# R220L.net
KiCad netlist of a schematic drawn in EAGLE
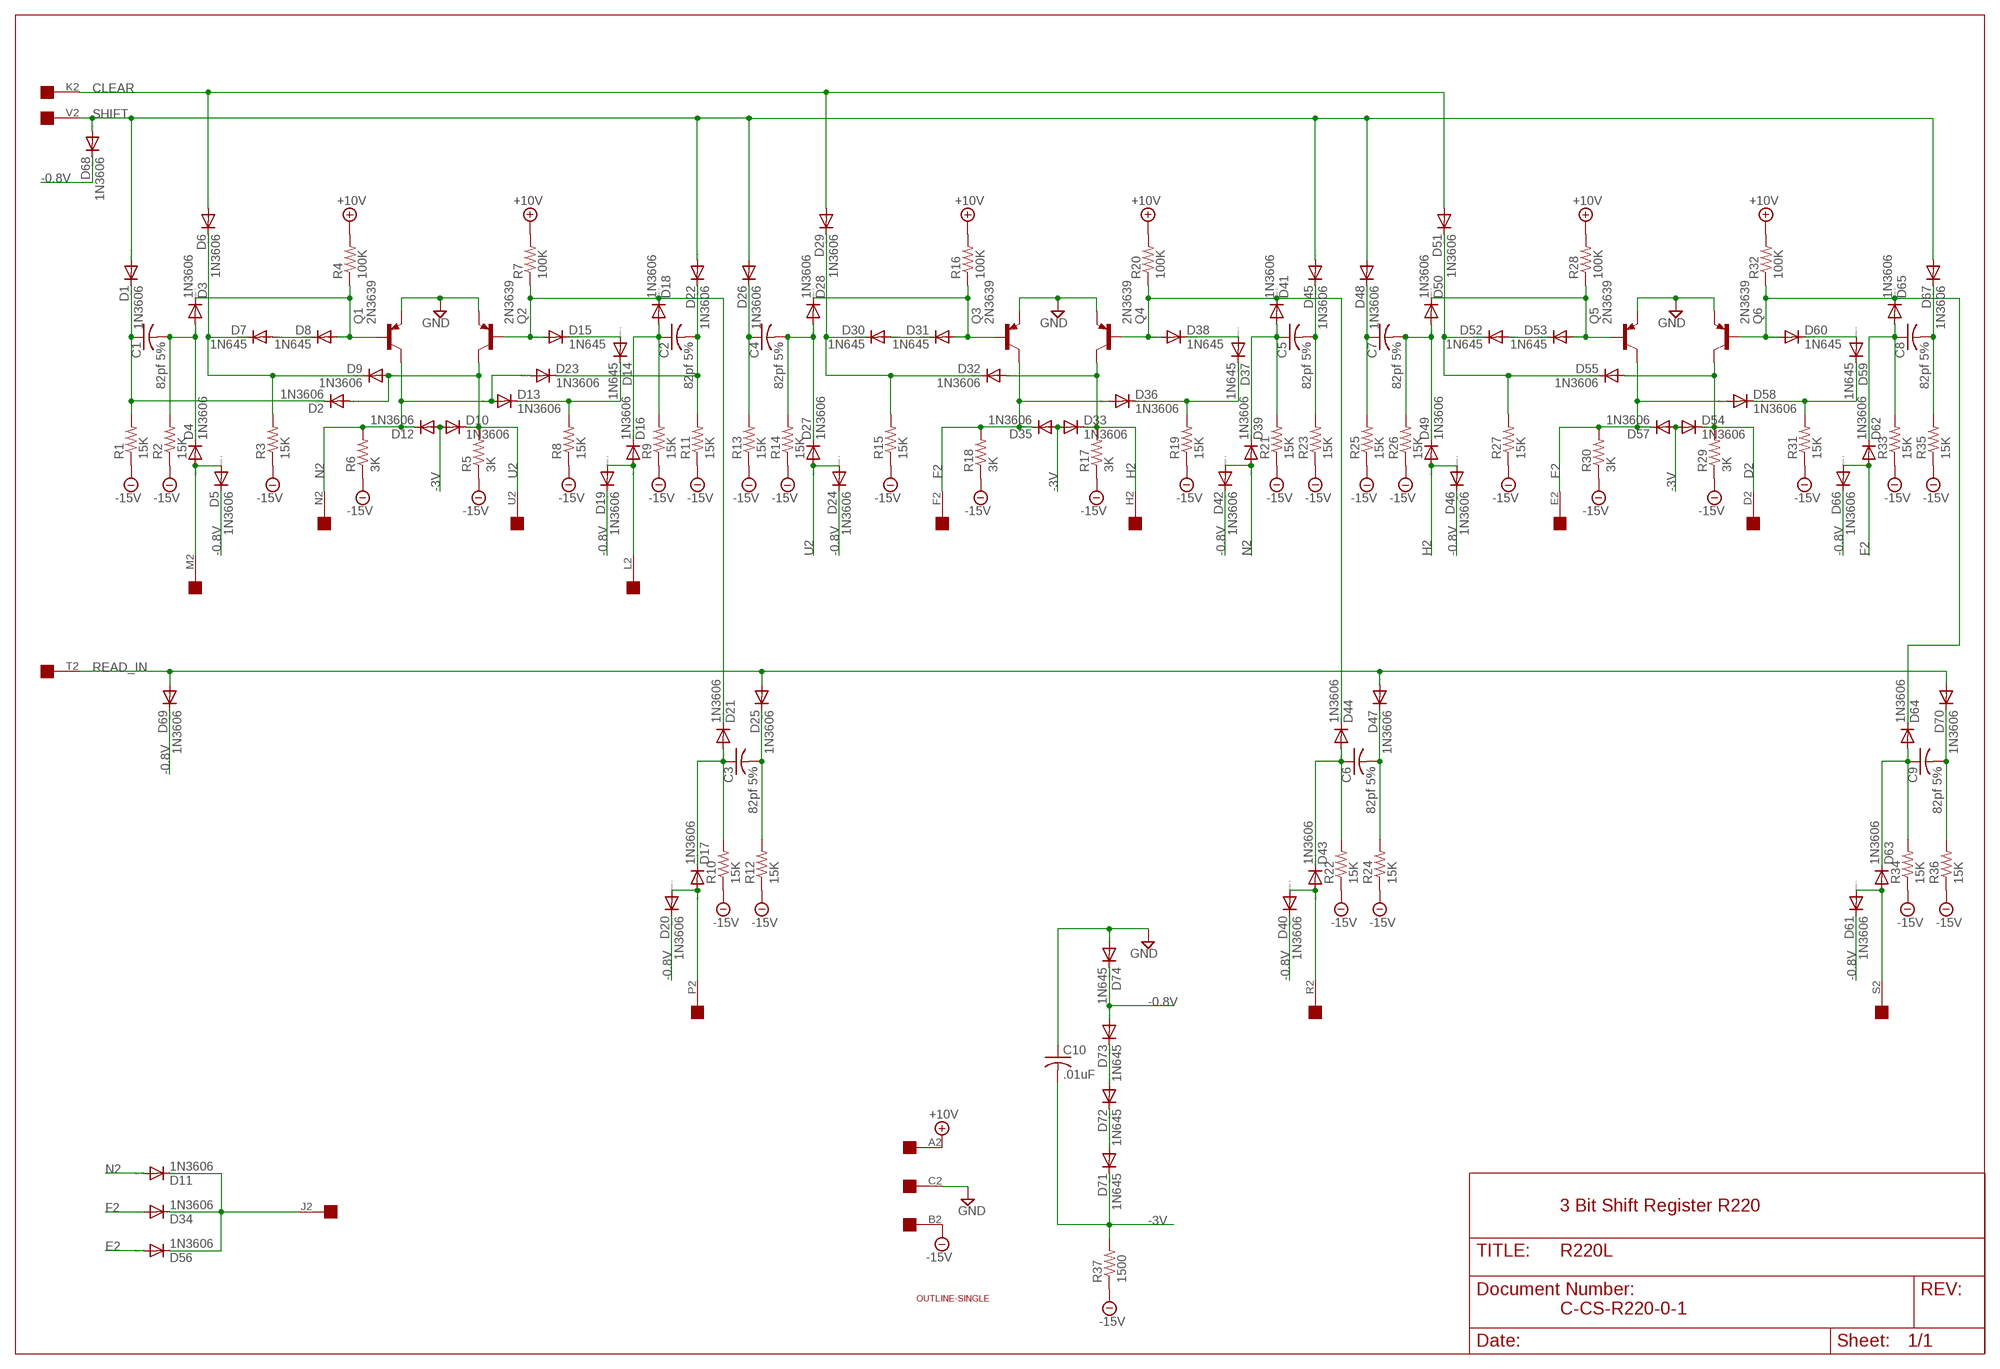
[diagram p0: schematic, sheet 1]

(export (version "E")
  (design (tool "Eeschema 10.0.6"))
  (components
    (comp (ref "C1")
      (value "82pf 5%")
      (footprint "eagle-import:C063-025X075")
      (libsource (lib "eagle-import") (part "C-US"))
    )
    (comp (ref "C2")
      (value "82pf 5%")
      (footprint "eagle-import:C063-025X075")
      (libsource (lib "eagle-import") (part "C-US"))
    )
    (comp (ref "C3")
      (value "82pf 5%")
      (footprint "eagle-import:C063-025X075")
      (libsource (lib "eagle-import") (part "C-US"))
    )
    (comp (ref "C4")
      (value "82pf 5%")
      (footprint "eagle-import:C063-025X075")
      (libsource (lib "eagle-import") (part "C-US"))
    )
    (comp (ref "C5")
      (value "82pf 5%")
      (footprint "eagle-import:C063-025X075")
      (libsource (lib "eagle-import") (part "C-US"))
    )
    (comp (ref "C6")
      (value "82pf 5%")
      (footprint "eagle-import:C063-025X075")
      (libsource (lib "eagle-import") (part "C-US"))
    )
    (comp (ref "C7")
      (value "82pf 5%")
      (footprint "eagle-import:C063-025X075")
      (libsource (lib "eagle-import") (part "C-US"))
    )
    (comp (ref "C8")
      (value "82pf 5%")
      (footprint "eagle-import:C063-025X075")
      (libsource (lib "eagle-import") (part "C-US"))
    )
    (comp (ref "C9")
      (value "82pf 5%")
      (footprint "eagle-import:C063-025X075")
      (libsource (lib "eagle-import") (part "C-US"))
    )
    (comp (ref "C10")
      (value ".01uF")
      (footprint "eagle-import:C063-025X075")
      (libsource (lib "eagle-import") (part "C-US"))
    )
    (comp (ref "D1")
      (value "1N3606")
      (footprint "eagle-import:DO35-10")
      (libsource (lib "eagle-import") (part "1N4148DO35-10"))
    )
    (comp (ref "D2")
      (value "1N3606")
      (footprint "eagle-import:DO35-10")
      (libsource (lib "eagle-import") (part "1N4148DO35-10"))
    )
    (comp (ref "D3")
      (value "1N3606")
      (footprint "eagle-import:DO35-10")
      (libsource (lib "eagle-import") (part "1N4148DO35-10"))
    )
    (comp (ref "D4")
      (value "1N3606")
      (footprint "eagle-import:DO35-10")
      (libsource (lib "eagle-import") (part "1N4148DO35-10"))
    )
    (comp (ref "D5")
      (value "1N3606")
      (footprint "eagle-import:DO35-10")
      (libsource (lib "eagle-import") (part "1N4148DO35-10"))
    )
    (comp (ref "D6")
      (value "1N3606")
      (footprint "eagle-import:DO35-10")
      (libsource (lib "eagle-import") (part "1N4148DO35-10"))
    )
    (comp (ref "D7")
      (value "1N645")
      (footprint "eagle-import:DO35-10")
      (libsource (lib "eagle-import") (part "1N4148DO35-10"))
    )
    (comp (ref "D8")
      (value "1N645")
      (footprint "eagle-import:DO35-10")
      (libsource (lib "eagle-import") (part "1N4148DO35-10"))
    )
    (comp (ref "D9")
      (value "1N3606")
      (footprint "eagle-import:DO35-10")
      (libsource (lib "eagle-import") (part "1N4148DO35-10"))
    )
    (comp (ref "D10")
      (value "1N3606")
      (footprint "eagle-import:DO35-10")
      (libsource (lib "eagle-import") (part "1N4148DO35-10"))
    )
    (comp (ref "D11")
      (value "1N3606")
      (footprint "eagle-import:DO35-10")
      (libsource (lib "eagle-import") (part "1N4148DO35-10"))
    )
    (comp (ref "D12")
      (value "1N3606")
      (footprint "eagle-import:DO35-10")
      (libsource (lib "eagle-import") (part "1N4148DO35-10"))
    )
    (comp (ref "D13")
      (value "1N3606")
      (footprint "eagle-import:DO35-10")
      (libsource (lib "eagle-import") (part "1N4148DO35-10"))
    )
    (comp (ref "D14")
      (value "1N645")
      (footprint "eagle-import:DO35-10")
      (libsource (lib "eagle-import") (part "1N4148DO35-10"))
    )
    (comp (ref "D15")
      (value "1N645")
      (footprint "eagle-import:DO35-10")
      (libsource (lib "eagle-import") (part "1N4148DO35-10"))
    )
    (comp (ref "D16")
      (value "1N3606")
      (footprint "eagle-import:DO35-10")
      (libsource (lib "eagle-import") (part "1N4148DO35-10"))
    )
    (comp (ref "D17")
      (value "1N3606")
      (footprint "eagle-import:DO35-10")
      (libsource (lib "eagle-import") (part "1N4148DO35-10"))
    )
    (comp (ref "D18")
      (value "1N3606")
      (footprint "eagle-import:DO35-10")
      (libsource (lib "eagle-import") (part "1N4148DO35-10"))
    )
    (comp (ref "D19")
      (value "1N3606")
      (footprint "eagle-import:DO35-10")
      (libsource (lib "eagle-import") (part "1N4148DO35-10"))
    )
    (comp (ref "D20")
      (value "1N3606")
      (footprint "eagle-import:DO35-10")
      (libsource (lib "eagle-import") (part "1N4148DO35-10"))
    )
    (comp (ref "D21")
      (value "1N3606")
      (footprint "eagle-import:DO35-10")
      (libsource (lib "eagle-import") (part "1N4148DO35-10"))
    )
    (comp (ref "D22")
      (value "1N3606")
      (footprint "eagle-import:DO35-10")
      (libsource (lib "eagle-import") (part "1N4148DO35-10"))
    )
    (comp (ref "D23")
      (value "1N3606")
      (footprint "eagle-import:DO35-10")
      (libsource (lib "eagle-import") (part "1N4148DO35-10"))
    )
    (comp (ref "D24")
      (value "1N3606")
      (footprint "eagle-import:DO35-10")
      (libsource (lib "eagle-import") (part "1N4148DO35-10"))
    )
    (comp (ref "D25")
      (value "1N3606")
      (footprint "eagle-import:DO35-10")
      (libsource (lib "eagle-import") (part "1N4148DO35-10"))
    )
    (comp (ref "D26")
      (value "1N3606")
      (footprint "eagle-import:DO35-10")
      (libsource (lib "eagle-import") (part "1N4148DO35-10"))
    )
    (comp (ref "D27")
      (value "1N3606")
      (footprint "eagle-import:DO35-10")
      (libsource (lib "eagle-import") (part "1N4148DO35-10"))
    )
    (comp (ref "D28")
      (value "1N3606")
      (footprint "eagle-import:DO35-10")
      (libsource (lib "eagle-import") (part "1N4148DO35-10"))
    )
    (comp (ref "D29")
      (value "1N3606")
      (footprint "eagle-import:DO35-10")
      (libsource (lib "eagle-import") (part "1N4148DO35-10"))
    )
    (comp (ref "D30")
      (value "1N645")
      (footprint "eagle-import:DO35-10")
      (libsource (lib "eagle-import") (part "1N4148DO35-10"))
    )
    (comp (ref "D31")
      (value "1N645")
      (footprint "eagle-import:DO35-10")
      (libsource (lib "eagle-import") (part "1N4148DO35-10"))
    )
    (comp (ref "D32")
      (value "1N3606")
      (footprint "eagle-import:DO35-10")
      (libsource (lib "eagle-import") (part "1N4148DO35-10"))
    )
    (comp (ref "D33")
      (value "1N3606")
      (footprint "eagle-import:DO35-10")
      (libsource (lib "eagle-import") (part "1N4148DO35-10"))
    )
    (comp (ref "D34")
      (value "1N3606")
      (footprint "eagle-import:DO35-10")
      (libsource (lib "eagle-import") (part "1N4148DO35-10"))
    )
    (comp (ref "D35")
      (value "1N3606")
      (footprint "eagle-import:DO35-10")
      (libsource (lib "eagle-import") (part "1N4148DO35-10"))
    )
    (comp (ref "D36")
      (value "1N3606")
      (footprint "eagle-import:DO35-10")
      (libsource (lib "eagle-import") (part "1N4148DO35-10"))
    )
    (comp (ref "D37")
      (value "1N645")
      (footprint "eagle-import:DO35-10")
      (libsource (lib "eagle-import") (part "1N4148DO35-10"))
    )
    (comp (ref "D38")
      (value "1N645")
      (footprint "eagle-import:DO35-10")
      (libsource (lib "eagle-import") (part "1N4148DO35-10"))
    )
    (comp (ref "D39")
      (value "1N3606")
      (footprint "eagle-import:DO35-10")
      (libsource (lib "eagle-import") (part "1N4148DO35-10"))
    )
    (comp (ref "D40")
      (value "1N3606")
      (footprint "eagle-import:DO35-10")
      (libsource (lib "eagle-import") (part "1N4148DO35-10"))
    )
    (comp (ref "D41")
      (value "1N3606")
      (footprint "eagle-import:DO35-10")
      (libsource (lib "eagle-import") (part "1N4148DO35-10"))
    )
    (comp (ref "D42")
      (value "1N3606")
      (footprint "eagle-import:DO35-10")
      (libsource (lib "eagle-import") (part "1N4148DO35-10"))
    )
    (comp (ref "D43")
      (value "1N3606")
      (footprint "eagle-import:DO35-10")
      (libsource (lib "eagle-import") (part "1N4148DO35-10"))
    )
    (comp (ref "D44")
      (value "1N3606")
      (footprint "eagle-import:DO35-10")
      (libsource (lib "eagle-import") (part "1N4148DO35-10"))
    )
    (comp (ref "D45")
      (value "1N3606")
      (footprint "eagle-import:DO35-10")
      (libsource (lib "eagle-import") (part "1N4148DO35-10"))
    )
    (comp (ref "D46")
      (value "1N3606")
      (footprint "eagle-import:DO35-10")
      (libsource (lib "eagle-import") (part "1N4148DO35-10"))
    )
    (comp (ref "D47")
      (value "1N3606")
      (footprint "eagle-import:DO35-10")
      (libsource (lib "eagle-import") (part "1N4148DO35-10"))
    )
    (comp (ref "D48")
      (value "1N3606")
      (footprint "eagle-import:DO35-10")
      (libsource (lib "eagle-import") (part "1N4148DO35-10"))
    )
    (comp (ref "D49")
      (value "1N3606")
      (footprint "eagle-import:DO35-10")
      (libsource (lib "eagle-import") (part "1N4148DO35-10"))
    )
    (comp (ref "D50")
      (value "1N3606")
      (footprint "eagle-import:DO35-10")
      (libsource (lib "eagle-import") (part "1N4148DO35-10"))
    )
    (comp (ref "D51")
      (value "1N3606")
      (footprint "eagle-import:DO35-10")
      (libsource (lib "eagle-import") (part "1N4148DO35-10"))
    )
    (comp (ref "D52")
      (value "1N645")
      (footprint "eagle-import:DO35-10")
      (libsource (lib "eagle-import") (part "1N4148DO35-10"))
    )
    (comp (ref "D53")
      (value "1N645")
      (footprint "eagle-import:DO35-10")
      (libsource (lib "eagle-import") (part "1N4148DO35-10"))
    )
    (comp (ref "D54")
      (value "1N3606")
      (footprint "eagle-import:DO35-10")
      (libsource (lib "eagle-import") (part "1N4148DO35-10"))
    )
    (comp (ref "D55")
      (value "1N3606")
      (footprint "eagle-import:DO35-10")
      (libsource (lib "eagle-import") (part "1N4148DO35-10"))
    )
    (comp (ref "D56")
      (value "1N3606")
      (footprint "eagle-import:DO35-10")
      (libsource (lib "eagle-import") (part "1N4148DO35-10"))
    )
    (comp (ref "D57")
      (value "1N3606")
      (footprint "eagle-import:DO35-10")
      (libsource (lib "eagle-import") (part "1N4148DO35-10"))
    )
    (comp (ref "D58")
      (value "1N3606")
      (footprint "eagle-import:DO35-10")
      (libsource (lib "eagle-import") (part "1N4148DO35-10"))
    )
    (comp (ref "D59")
      (value "1N645")
      (footprint "eagle-import:DO35-10")
      (libsource (lib "eagle-import") (part "1N4148DO35-10"))
    )
    (comp (ref "D60")
      (value "1N645")
      (footprint "eagle-import:DO35-10")
      (libsource (lib "eagle-import") (part "1N4148DO35-10"))
    )
    (comp (ref "D61")
      (value "1N3606")
      (footprint "eagle-import:DO35-10")
      (libsource (lib "eagle-import") (part "1N4148DO35-10"))
    )
    (comp (ref "D62")
      (value "1N3606")
      (footprint "eagle-import:DO35-10")
      (libsource (lib "eagle-import") (part "1N4148DO35-10"))
    )
    (comp (ref "D63")
      (value "1N3606")
      (footprint "eagle-import:DO35-10")
      (libsource (lib "eagle-import") (part "1N4148DO35-10"))
    )
    (comp (ref "D64")
      (value "1N3606")
      (footprint "eagle-import:DO35-10")
      (libsource (lib "eagle-import") (part "1N4148DO35-10"))
    )
    (comp (ref "D65")
      (value "1N3606")
      (footprint "eagle-import:DO35-10")
      (libsource (lib "eagle-import") (part "1N4148DO35-10"))
    )
    (comp (ref "D66")
      (value "1N3606")
      (footprint "eagle-import:DO35-10")
      (libsource (lib "eagle-import") (part "1N4148DO35-10"))
    )
    (comp (ref "D67")
      (value "1N3606")
      (footprint "eagle-import:DO35-10")
      (libsource (lib "eagle-import") (part "1N4148DO35-10"))
    )
    (comp (ref "D68")
      (value "1N3606")
      (footprint "eagle-import:DO35-10")
      (libsource (lib "eagle-import") (part "1N4148DO35-10"))
    )
    (comp (ref "D69")
      (value "1N3606")
      (footprint "eagle-import:DO35-10")
      (libsource (lib "eagle-import") (part "1N4148DO35-10"))
    )
    (comp (ref "D70")
      (value "1N3606")
      (footprint "eagle-import:DO35-10")
      (libsource (lib "eagle-import") (part "1N4148DO35-10"))
    )
    (comp (ref "D71")
      (value "1N645")
      (footprint "eagle-import:DO35-10")
      (libsource (lib "eagle-import") (part "1N4148DO35-10"))
    )
    (comp (ref "D72")
      (value "1N645")
      (footprint "eagle-import:DO35-10")
      (libsource (lib "eagle-import") (part "1N4148DO35-10"))
    )
    (comp (ref "D73")
      (value "1N645")
      (footprint "eagle-import:DO35-10")
      (libsource (lib "eagle-import") (part "1N4148DO35-10"))
    )
    (comp (ref "D74")
      (value "1N645")
      (footprint "eagle-import:DO35-10")
      (libsource (lib "eagle-import") (part "1N4148DO35-10"))
    )
    (comp (ref "Q1")
      (value "2N3639")
      (footprint "eagle-import:TO39")
      (libsource (lib "eagle-import") (part "2N3637"))
    )
    (comp (ref "Q2")
      (value "2N3639")
      (footprint "eagle-import:TO39")
      (libsource (lib "eagle-import") (part "2N3637"))
    )
    (comp (ref "Q3")
      (value "2N3639")
      (footprint "eagle-import:TO39")
      (libsource (lib "eagle-import") (part "2N3637"))
    )
    (comp (ref "Q4")
      (value "2N3639")
      (footprint "eagle-import:TO39")
      (libsource (lib "eagle-import") (part "2N3637"))
    )
    (comp (ref "Q5")
      (value "2N3639")
      (footprint "eagle-import:TO39")
      (libsource (lib "eagle-import") (part "2N3637"))
    )
    (comp (ref "Q6")
      (value "2N3639")
      (footprint "eagle-import:TO39")
      (libsource (lib "eagle-import") (part "2N3637"))
    )
    (comp (ref "R1")
      (value "15K")
      (footprint "eagle-import:0207_10")
      (libsource (lib "eagle-import") (part "R-US_0207/10"))
    )
    (comp (ref "R2")
      (value "15K")
      (footprint "eagle-import:0207_10")
      (libsource (lib "eagle-import") (part "R-US_0207/10"))
    )
    (comp (ref "R3")
      (value "15K")
      (footprint "eagle-import:0207_10")
      (libsource (lib "eagle-import") (part "R-US_0207/10"))
    )
    (comp (ref "R4")
      (value "100K")
      (footprint "eagle-import:0207_10")
      (libsource (lib "eagle-import") (part "R-US_0207/10"))
    )
    (comp (ref "R5")
      (value "3K")
      (footprint "eagle-import:0207_10")
      (libsource (lib "eagle-import") (part "R-US_0207/10"))
    )
    (comp (ref "R6")
      (value "3K")
      (footprint "eagle-import:0207_10")
      (libsource (lib "eagle-import") (part "R-US_0207/10"))
    )
    (comp (ref "R7")
      (value "100K")
      (footprint "eagle-import:0207_10")
      (libsource (lib "eagle-import") (part "R-US_0207/10"))
    )
    (comp (ref "R8")
      (value "15K")
      (footprint "eagle-import:0207_10")
      (libsource (lib "eagle-import") (part "R-US_0207/10"))
    )
    (comp (ref "R9")
      (value "15K")
      (footprint "eagle-import:0207_10")
      (libsource (lib "eagle-import") (part "R-US_0207/10"))
    )
    (comp (ref "R10")
      (value "15K")
      (footprint "eagle-import:0207_10")
      (libsource (lib "eagle-import") (part "R-US_0207/10"))
    )
    (comp (ref "R11")
      (value "15K")
      (footprint "eagle-import:0207_10")
      (libsource (lib "eagle-import") (part "R-US_0207/10"))
    )
    (comp (ref "R12")
      (value "15K")
      (footprint "eagle-import:0207_10")
      (libsource (lib "eagle-import") (part "R-US_0207/10"))
    )
    (comp (ref "R13")
      (value "15K")
      (footprint "eagle-import:0207_10")
      (libsource (lib "eagle-import") (part "R-US_0207/10"))
    )
    (comp (ref "R14")
      (value "15K")
      (footprint "eagle-import:0207_10")
      (libsource (lib "eagle-import") (part "R-US_0207/10"))
    )
    (comp (ref "R15")
      (value "15K")
      (footprint "eagle-import:0207_10")
      (libsource (lib "eagle-import") (part "R-US_0207/10"))
    )
    (comp (ref "R16")
      (value "100K")
      (footprint "eagle-import:0207_10")
      (libsource (lib "eagle-import") (part "R-US_0207/10"))
    )
    (comp (ref "R17")
      (value "3K")
      (footprint "eagle-import:0207_10")
      (libsource (lib "eagle-import") (part "R-US_0207/10"))
    )
    (comp (ref "R18")
      (value "3K")
      (footprint "eagle-import:0207_10")
      (libsource (lib "eagle-import") (part "R-US_0207/10"))
    )
    (comp (ref "R19")
      (value "15K")
      (footprint "eagle-import:0207_10")
      (libsource (lib "eagle-import") (part "R-US_0207/10"))
    )
    (comp (ref "R20")
      (value "100K")
      (footprint "eagle-import:0207_10")
      (libsource (lib "eagle-import") (part "R-US_0207/10"))
    )
    (comp (ref "R21")
      (value "15K")
      (footprint "eagle-import:0207_10")
      (libsource (lib "eagle-import") (part "R-US_0207/10"))
    )
    (comp (ref "R22")
      (value "15K")
      (footprint "eagle-import:0207_10")
      (libsource (lib "eagle-import") (part "R-US_0207/10"))
    )
    (comp (ref "R23")
      (value "15K")
      (footprint "eagle-import:0207_10")
      (libsource (lib "eagle-import") (part "R-US_0207/10"))
    )
    (comp (ref "R24")
      (value "15K")
      (footprint "eagle-import:0207_10")
      (libsource (lib "eagle-import") (part "R-US_0207/10"))
    )
    (comp (ref "R25")
      (value "15K")
      (footprint "eagle-import:0207_10")
      (libsource (lib "eagle-import") (part "R-US_0207/10"))
    )
    (comp (ref "R26")
      (value "15K")
      (footprint "eagle-import:0207_10")
      (libsource (lib "eagle-import") (part "R-US_0207/10"))
    )
    (comp (ref "R27")
      (value "15K")
      (footprint "eagle-import:0207_10")
      (libsource (lib "eagle-import") (part "R-US_0207/10"))
    )
    (comp (ref "R28")
      (value "100K")
      (footprint "eagle-import:0207_10")
      (libsource (lib "eagle-import") (part "R-US_0207/10"))
    )
    (comp (ref "R29")
      (value "3K")
      (footprint "eagle-import:0207_10")
      (libsource (lib "eagle-import") (part "R-US_0207/10"))
    )
    (comp (ref "R30")
      (value "3K")
      (footprint "eagle-import:0207_10")
      (libsource (lib "eagle-import") (part "R-US_0207/10"))
    )
    (comp (ref "R31")
      (value "15K")
      (footprint "eagle-import:0207_10")
      (libsource (lib "eagle-import") (part "R-US_0207/10"))
    )
    (comp (ref "R32")
      (value "100K")
      (footprint "eagle-import:0207_10")
      (libsource (lib "eagle-import") (part "R-US_0207/10"))
    )
    (comp (ref "R33")
      (value "15K")
      (footprint "eagle-import:0207_10")
      (libsource (lib "eagle-import") (part "R-US_0207/10"))
    )
    (comp (ref "R34")
      (value "15K")
      (footprint "eagle-import:0207_10")
      (libsource (lib "eagle-import") (part "R-US_0207/10"))
    )
    (comp (ref "R35")
      (value "15K")
      (footprint "eagle-import:0207_10")
      (libsource (lib "eagle-import") (part "R-US_0207/10"))
    )
    (comp (ref "R36")
      (value "15K")
      (footprint "eagle-import:0207_10")
      (libsource (lib "eagle-import") (part "R-US_0207/10"))
    )
    (comp (ref "R37")
      (value "1500")
      (footprint "eagle-import:0207_10")
      (libsource (lib "eagle-import") (part "R-US_0207/10"))
    )
    (comp (ref "U$1")
      (value "OUTLINE-SINGLE")
      (footprint "eagle-import:SINGLE")
      (libsource (lib "eagle-import") (part "OUTLINE-SINGLE"))
    )
    (comp (ref "U$2")
      (value "EDGE-1")
      (footprint "eagle-import:EDGE-CON1")
      (libsource (lib "eagle-import") (part "EDGE-1"))
    )
  )
  (nets
    (net (code "1") (name "+10V") (class "Default")
      (node (ref "R16") (pin "2") (pinfunction "2_2") (pintype "passive"))
      (node (ref "R20") (pin "2") (pinfunction "2_2") (pintype "passive"))
      (node (ref "R28") (pin "2") (pinfunction "2_2") (pintype "passive"))
      (node (ref "R32") (pin "2") (pinfunction "2_2") (pintype "passive"))
      (node (ref "R4") (pin "2") (pinfunction "2_2") (pintype "passive"))
      (node (ref "R7") (pin "2") (pinfunction "2_2") (pintype "passive"))
      (node (ref "U$2") (pin "A2") (pinfunction "1_A2") (pintype "bidirectional"))
    )
    (net (code "2") (name "-15V") (class "Default")
      (node (ref "R1") (pin "1") (pinfunction "1_1") (pintype "passive"))
      (node (ref "R10") (pin "1") (pinfunction "1_1") (pintype "passive"))
      (node (ref "R11") (pin "1") (pinfunction "1_1") (pintype "passive"))
      (node (ref "R12") (pin "1") (pinfunction "1_1") (pintype "passive"))
      (node (ref "R13") (pin "1") (pinfunction "1_1") (pintype "passive"))
      (node (ref "R14") (pin "1") (pinfunction "1_1") (pintype "passive"))
      (node (ref "R15") (pin "1") (pinfunction "1_1") (pintype "passive"))
      (node (ref "R17") (pin "1") (pinfunction "1_1") (pintype "passive"))
      (node (ref "R18") (pin "1") (pinfunction "1_1") (pintype "passive"))
      (node (ref "R19") (pin "1") (pinfunction "1_1") (pintype "passive"))
      (node (ref "R2") (pin "1") (pinfunction "1_1") (pintype "passive"))
      (node (ref "R21") (pin "1") (pinfunction "1_1") (pintype "passive"))
      (node (ref "R22") (pin "1") (pinfunction "1_1") (pintype "passive"))
      (node (ref "R23") (pin "1") (pinfunction "1_1") (pintype "passive"))
      (node (ref "R24") (pin "1") (pinfunction "1_1") (pintype "passive"))
      (node (ref "R25") (pin "1") (pinfunction "1_1") (pintype "passive"))
      (node (ref "R26") (pin "1") (pinfunction "1_1") (pintype "passive"))
      (node (ref "R27") (pin "1") (pinfunction "1_1") (pintype "passive"))
      (node (ref "R29") (pin "1") (pinfunction "1_1") (pintype "passive"))
      (node (ref "R3") (pin "1") (pinfunction "1_1") (pintype "passive"))
      (node (ref "R30") (pin "1") (pinfunction "1_1") (pintype "passive"))
      (node (ref "R31") (pin "1") (pinfunction "1_1") (pintype "passive"))
      (node (ref "R33") (pin "1") (pinfunction "1_1") (pintype "passive"))
      (node (ref "R34") (pin "1") (pinfunction "1_1") (pintype "passive"))
      (node (ref "R35") (pin "1") (pinfunction "1_1") (pintype "passive"))
      (node (ref "R36") (pin "1") (pinfunction "1_1") (pintype "passive"))
      (node (ref "R37") (pin "1") (pinfunction "1_1") (pintype "passive"))
      (node (ref "R5") (pin "1") (pinfunction "1_1") (pintype "passive"))
      (node (ref "R6") (pin "1") (pinfunction "1_1") (pintype "passive"))
      (node (ref "R8") (pin "1") (pinfunction "1_1") (pintype "passive"))
      (node (ref "R9") (pin "1") (pinfunction "1_1") (pintype "passive"))
      (node (ref "U$2") (pin "B2") (pinfunction "1_B2") (pintype "bidirectional"))
    )
    (net (code "3") (name "/-0.8V") (class "Default")
      (node (ref "D19") (pin "C") (pinfunction "C_C") (pintype "passive"))
      (node (ref "D20") (pin "C") (pinfunction "C_C") (pintype "passive"))
      (node (ref "D24") (pin "C") (pinfunction "C_C") (pintype "passive"))
      (node (ref "D40") (pin "C") (pinfunction "C_C") (pintype "passive"))
      (node (ref "D42") (pin "C") (pinfunction "C_C") (pintype "passive"))
      (node (ref "D46") (pin "C") (pinfunction "C_C") (pintype "passive"))
      (node (ref "D5") (pin "C") (pinfunction "C_C") (pintype "passive"))
      (node (ref "D61") (pin "C") (pinfunction "C_C") (pintype "passive"))
      (node (ref "D66") (pin "C") (pinfunction "C_C") (pintype "passive"))
      (node (ref "D68") (pin "C") (pinfunction "C_C") (pintype "passive"))
      (node (ref "D69") (pin "C") (pinfunction "C_C") (pintype "passive"))
      (node (ref "D73") (pin "A") (pinfunction "A_A") (pintype "passive"))
      (node (ref "D74") (pin "C") (pinfunction "C_C") (pintype "passive"))
    )
    (net (code "4") (name "/-3V") (class "Default")
      (node (ref "C10") (pin "2") (pinfunction "2_2") (pintype "passive"))
      (node (ref "D10") (pin "A") (pinfunction "A_A") (pintype "passive"))
      (node (ref "D12") (pin "A") (pinfunction "A_A") (pintype "passive"))
      (node (ref "D33") (pin "A") (pinfunction "A_A") (pintype "passive"))
      (node (ref "D35") (pin "A") (pinfunction "A_A") (pintype "passive"))
      (node (ref "D54") (pin "A") (pinfunction "A_A") (pintype "passive"))
      (node (ref "D57") (pin "A") (pinfunction "A_A") (pintype "passive"))
      (node (ref "D71") (pin "C") (pinfunction "C_C") (pintype "passive"))
      (node (ref "R37") (pin "2") (pinfunction "2_2") (pintype "passive"))
    )
    (net (code "5") (name "/CLEAR") (class "Default")
      (node (ref "D29") (pin "A") (pinfunction "A_A") (pintype "passive"))
      (node (ref "D51") (pin "A") (pinfunction "A_A") (pintype "passive"))
      (node (ref "D6") (pin "A") (pinfunction "A_A") (pintype "passive"))
      (node (ref "U$2") (pin "K2") (pinfunction "1_K2") (pintype "bidirectional"))
    )
    (net (code "6") (name "/D2") (class "Default")
      (node (ref "D54") (pin "C") (pinfunction "C_C") (pintype "passive"))
      (node (ref "D55") (pin "A") (pinfunction "A_A") (pintype "passive"))
      (node (ref "Q6") (pin "3") (pinfunction "C_3") (pintype "passive"))
      (node (ref "R29") (pin "2") (pinfunction "2_2") (pintype "passive"))
      (node (ref "U$2") (pin "D2") (pinfunction "1_D2") (pintype "bidirectional"))
    )
    (net (code "7") (name "/E2") (class "Default")
      (node (ref "D56") (pin "A") (pinfunction "A_A") (pintype "passive"))
      (node (ref "D57") (pin "C") (pinfunction "C_C") (pintype "passive"))
      (node (ref "D58") (pin "A") (pinfunction "A_A") (pintype "passive"))
      (node (ref "Q5") (pin "3") (pinfunction "C_3") (pintype "passive"))
      (node (ref "R30") (pin "2") (pinfunction "2_2") (pintype "passive"))
      (node (ref "U$2") (pin "E2") (pinfunction "1_E2") (pintype "bidirectional"))
    )
    (net (code "8") (name "/F2") (class "Default")
      (node (ref "D34") (pin "A") (pinfunction "A_A") (pintype "passive"))
      (node (ref "D35") (pin "C") (pinfunction "C_C") (pintype "passive"))
      (node (ref "D36") (pin "A") (pinfunction "A_A") (pintype "passive"))
      (node (ref "D62") (pin "A") (pinfunction "A_A") (pintype "passive"))
      (node (ref "D66") (pin "A") (pinfunction "A_A") (pintype "passive"))
      (node (ref "Q3") (pin "3") (pinfunction "C_3") (pintype "passive"))
      (node (ref "R18") (pin "2") (pinfunction "2_2") (pintype "passive"))
      (node (ref "U$2") (pin "F2") (pinfunction "1_F2") (pintype "bidirectional"))
    )
    (net (code "9") (name "/H2") (class "Default")
      (node (ref "D32") (pin "A") (pinfunction "A_A") (pintype "passive"))
      (node (ref "D33") (pin "C") (pinfunction "C_C") (pintype "passive"))
      (node (ref "D46") (pin "A") (pinfunction "A_A") (pintype "passive"))
      (node (ref "D49") (pin "A") (pinfunction "A_A") (pintype "passive"))
      (node (ref "Q4") (pin "3") (pinfunction "C_3") (pintype "passive"))
      (node (ref "R17") (pin "2") (pinfunction "2_2") (pintype "passive"))
      (node (ref "U$2") (pin "H2") (pinfunction "1_H2") (pintype "bidirectional"))
    )
    (net (code "10") (name "/N2") (class "Default")
      (node (ref "D11") (pin "A") (pinfunction "A_A") (pintype "passive"))
      (node (ref "D12") (pin "C") (pinfunction "C_C") (pintype "passive"))
      (node (ref "D13") (pin "A") (pinfunction "A_A") (pintype "passive"))
      (node (ref "D23") (pin "A") (pinfunction "A_A") (pintype "passive"))
      (node (ref "D39") (pin "A") (pinfunction "A_A") (pintype "passive"))
      (node (ref "D42") (pin "A") (pinfunction "A_A") (pintype "passive"))
      (node (ref "Q1") (pin "3") (pinfunction "C_3") (pintype "passive"))
      (node (ref "R6") (pin "2") (pinfunction "2_2") (pintype "passive"))
      (node (ref "U$2") (pin "N2") (pinfunction "1_N2") (pintype "bidirectional"))
    )
    (net (code "11") (name "/READ_IN") (class "Default")
      (node (ref "D25") (pin "A") (pinfunction "A_A") (pintype "passive"))
      (node (ref "D47") (pin "A") (pinfunction "A_A") (pintype "passive"))
      (node (ref "D69") (pin "A") (pinfunction "A_A") (pintype "passive"))
      (node (ref "D70") (pin "A") (pinfunction "A_A") (pintype "passive"))
      (node (ref "U$2") (pin "T2") (pinfunction "1_T2") (pintype "bidirectional"))
    )
    (net (code "12") (name "/SHIFT") (class "Default")
      (node (ref "D1") (pin "A") (pinfunction "A_A") (pintype "passive"))
      (node (ref "D22") (pin "A") (pinfunction "A_A") (pintype "passive"))
      (node (ref "D26") (pin "A") (pinfunction "A_A") (pintype "passive"))
      (node (ref "D45") (pin "A") (pinfunction "A_A") (pintype "passive"))
      (node (ref "D48") (pin "A") (pinfunction "A_A") (pintype "passive"))
      (node (ref "D67") (pin "A") (pinfunction "A_A") (pintype "passive"))
      (node (ref "D68") (pin "A") (pinfunction "A_A") (pintype "passive"))
      (node (ref "U$2") (pin "V2") (pinfunction "1_V2") (pintype "bidirectional"))
    )
    (net (code "13") (name "/U2") (class "Default")
      (node (ref "D10") (pin "C") (pinfunction "C_C") (pintype "passive"))
      (node (ref "D2") (pin "A") (pinfunction "A_A") (pintype "passive"))
      (node (ref "D24") (pin "A") (pinfunction "A_A") (pintype "passive"))
      (node (ref "D27") (pin "A") (pinfunction "A_A") (pintype "passive"))
      (node (ref "D9") (pin "A") (pinfunction "A_A") (pintype "passive"))
      (node (ref "Q2") (pin "3") (pinfunction "C_3") (pintype "passive"))
      (node (ref "R5") (pin "2") (pinfunction "2_2") (pintype "passive"))
      (node (ref "U$2") (pin "U2") (pinfunction "1_U2") (pintype "bidirectional"))
    )
    (net (code "14") (name "GND") (class "Default")
      (node (ref "C10") (pin "1") (pinfunction "1_1") (pintype "passive"))
      (node (ref "D74") (pin "A") (pinfunction "A_A") (pintype "passive"))
      (node (ref "Q1") (pin "1") (pinfunction "E_1") (pintype "passive"))
      (node (ref "Q2") (pin "1") (pinfunction "E_1") (pintype "passive"))
      (node (ref "Q3") (pin "1") (pinfunction "E_1") (pintype "passive"))
      (node (ref "Q4") (pin "1") (pinfunction "E_1") (pintype "passive"))
      (node (ref "Q5") (pin "1") (pinfunction "E_1") (pintype "passive"))
      (node (ref "Q6") (pin "1") (pinfunction "E_1") (pintype "passive"))
      (node (ref "U$2") (pin "C2") (pinfunction "1_C2") (pintype "bidirectional"))
    )
    (net (code "15") (name "Net-(C1-Pad1)") (class "Default")
      (node (ref "C1") (pin "1") (pinfunction "1_1") (pintype "passive"))
      (node (ref "D1") (pin "C") (pinfunction "C_C") (pintype "passive"))
      (node (ref "D2") (pin "C") (pinfunction "C_C") (pintype "passive"))
      (node (ref "R1") (pin "2") (pinfunction "2_2") (pintype "passive"))
    )
    (net (code "16") (name "Net-(C1-Pad2)") (class "Default")
      (node (ref "C1") (pin "2") (pinfunction "2_2") (pintype "passive"))
      (node (ref "D3") (pin "A") (pinfunction "A_A") (pintype "passive"))
      (node (ref "D4") (pin "C") (pinfunction "C_C") (pintype "passive"))
      (node (ref "R2") (pin "2") (pinfunction "2_2") (pintype "passive"))
    )
    (net (code "17") (name "Net-(C2-Pad1)") (class "Default")
      (node (ref "C2") (pin "1") (pinfunction "1_1") (pintype "passive"))
      (node (ref "D16") (pin "C") (pinfunction "C_C") (pintype "passive"))
      (node (ref "D18") (pin "A") (pinfunction "A_A") (pintype "passive"))
      (node (ref "R9") (pin "2") (pinfunction "2_2") (pintype "passive"))
    )
    (net (code "18") (name "Net-(C2-Pad2)") (class "Default")
      (node (ref "C2") (pin "2") (pinfunction "2_2") (pintype "passive"))
      (node (ref "D22") (pin "C") (pinfunction "C_C") (pintype "passive"))
      (node (ref "D23") (pin "C") (pinfunction "C_C") (pintype "passive"))
      (node (ref "R11") (pin "2") (pinfunction "2_2") (pintype "passive"))
    )
    (net (code "19") (name "Net-(C3-Pad1)") (class "Default")
      (node (ref "C3") (pin "1") (pinfunction "1_1") (pintype "passive"))
      (node (ref "D17") (pin "C") (pinfunction "C_C") (pintype "passive"))
      (node (ref "D21") (pin "A") (pinfunction "A_A") (pintype "passive"))
      (node (ref "R10") (pin "2") (pinfunction "2_2") (pintype "passive"))
    )
    (net (code "20") (name "Net-(C3-Pad2)") (class "Default")
      (node (ref "C3") (pin "2") (pinfunction "2_2") (pintype "passive"))
      (node (ref "D25") (pin "C") (pinfunction "C_C") (pintype "passive"))
      (node (ref "R12") (pin "2") (pinfunction "2_2") (pintype "passive"))
    )
    (net (code "21") (name "Net-(C4-Pad1)") (class "Default")
      (node (ref "C4") (pin "1") (pinfunction "1_1") (pintype "passive"))
      (node (ref "D26") (pin "C") (pinfunction "C_C") (pintype "passive"))
      (node (ref "R13") (pin "2") (pinfunction "2_2") (pintype "passive"))
    )
    (net (code "22") (name "Net-(C4-Pad2)") (class "Default")
      (node (ref "C4") (pin "2") (pinfunction "2_2") (pintype "passive"))
      (node (ref "D27") (pin "C") (pinfunction "C_C") (pintype "passive"))
      (node (ref "D28") (pin "A") (pinfunction "A_A") (pintype "passive"))
      (node (ref "R14") (pin "2") (pinfunction "2_2") (pintype "passive"))
    )
    (net (code "23") (name "Net-(C5-Pad1)") (class "Default")
      (node (ref "C5") (pin "1") (pinfunction "1_1") (pintype "passive"))
      (node (ref "D39") (pin "C") (pinfunction "C_C") (pintype "passive"))
      (node (ref "D41") (pin "A") (pinfunction "A_A") (pintype "passive"))
      (node (ref "R21") (pin "2") (pinfunction "2_2") (pintype "passive"))
    )
    (net (code "24") (name "Net-(C5-Pad2)") (class "Default")
      (node (ref "C5") (pin "2") (pinfunction "2_2") (pintype "passive"))
      (node (ref "D45") (pin "C") (pinfunction "C_C") (pintype "passive"))
      (node (ref "R23") (pin "2") (pinfunction "2_2") (pintype "passive"))
    )
    (net (code "25") (name "Net-(C6-Pad1)") (class "Default")
      (node (ref "C6") (pin "1") (pinfunction "1_1") (pintype "passive"))
      (node (ref "D43") (pin "C") (pinfunction "C_C") (pintype "passive"))
      (node (ref "D44") (pin "A") (pinfunction "A_A") (pintype "passive"))
      (node (ref "R22") (pin "2") (pinfunction "2_2") (pintype "passive"))
    )
    (net (code "26") (name "Net-(C6-Pad2)") (class "Default")
      (node (ref "C6") (pin "2") (pinfunction "2_2") (pintype "passive"))
      (node (ref "D47") (pin "C") (pinfunction "C_C") (pintype "passive"))
      (node (ref "R24") (pin "2") (pinfunction "2_2") (pintype "passive"))
    )
    (net (code "27") (name "Net-(C7-Pad1)") (class "Default")
      (node (ref "C7") (pin "1") (pinfunction "1_1") (pintype "passive"))
      (node (ref "D48") (pin "C") (pinfunction "C_C") (pintype "passive"))
      (node (ref "R25") (pin "2") (pinfunction "2_2") (pintype "passive"))
    )
    (net (code "28") (name "Net-(C7-Pad2)") (class "Default")
      (node (ref "C7") (pin "2") (pinfunction "2_2") (pintype "passive"))
      (node (ref "D49") (pin "C") (pinfunction "C_C") (pintype "passive"))
      (node (ref "D50") (pin "A") (pinfunction "A_A") (pintype "passive"))
      (node (ref "R26") (pin "2") (pinfunction "2_2") (pintype "passive"))
    )
    (net (code "29") (name "Net-(C8-Pad1)") (class "Default")
      (node (ref "C8") (pin "1") (pinfunction "1_1") (pintype "passive"))
      (node (ref "D62") (pin "C") (pinfunction "C_C") (pintype "passive"))
      (node (ref "D65") (pin "A") (pinfunction "A_A") (pintype "passive"))
      (node (ref "R33") (pin "2") (pinfunction "2_2") (pintype "passive"))
    )
    (net (code "30") (name "Net-(C8-Pad2)") (class "Default")
      (node (ref "C8") (pin "2") (pinfunction "2_2") (pintype "passive"))
      (node (ref "D67") (pin "C") (pinfunction "C_C") (pintype "passive"))
      (node (ref "R35") (pin "2") (pinfunction "2_2") (pintype "passive"))
    )
    (net (code "31") (name "Net-(C9-Pad1)") (class "Default")
      (node (ref "C9") (pin "1") (pinfunction "1_1") (pintype "passive"))
      (node (ref "D63") (pin "C") (pinfunction "C_C") (pintype "passive"))
      (node (ref "D64") (pin "A") (pinfunction "A_A") (pintype "passive"))
      (node (ref "R34") (pin "2") (pinfunction "2_2") (pintype "passive"))
    )
    (net (code "32") (name "Net-(C9-Pad2)") (class "Default")
      (node (ref "C9") (pin "2") (pinfunction "2_2") (pintype "passive"))
      (node (ref "D70") (pin "C") (pinfunction "C_C") (pintype "passive"))
      (node (ref "R36") (pin "2") (pinfunction "2_2") (pintype "passive"))
    )
    (net (code "33") (name "Net-(D6-PadC)") (class "Default")
      (node (ref "D6") (pin "C") (pinfunction "C_C") (pintype "passive"))
      (node (ref "D7") (pin "C") (pinfunction "C_C") (pintype "passive"))
      (node (ref "D9") (pin "C") (pinfunction "C_C") (pintype "passive"))
      (node (ref "R3") (pin "2") (pinfunction "2_2") (pintype "passive"))
    )
    (net (code "34") (name "Net-(D7-PadA)") (class "Default")
      (node (ref "D7") (pin "A") (pinfunction "A_A") (pintype "passive"))
      (node (ref "D8") (pin "C") (pinfunction "C_C") (pintype "passive"))
    )
    (net (code "35") (name "Net-(D13-PadC)") (class "Default")
      (node (ref "D13") (pin "C") (pinfunction "C_C") (pintype "passive"))
      (node (ref "D14") (pin "C") (pinfunction "C_C") (pintype "passive"))
      (node (ref "R8") (pin "2") (pinfunction "2_2") (pintype "passive"))
    )
    (net (code "36") (name "Net-(D14-PadA)") (class "Default")
      (node (ref "D14") (pin "A") (pinfunction "A_A") (pintype "passive"))
      (node (ref "D15") (pin "C") (pinfunction "C_C") (pintype "passive"))
    )
    (net (code "37") (name "Net-(D29-PadC)") (class "Default")
      (node (ref "D29") (pin "C") (pinfunction "C_C") (pintype "passive"))
      (node (ref "D30") (pin "C") (pinfunction "C_C") (pintype "passive"))
      (node (ref "D32") (pin "C") (pinfunction "C_C") (pintype "passive"))
      (node (ref "R15") (pin "2") (pinfunction "2_2") (pintype "passive"))
    )
    (net (code "38") (name "Net-(D30-PadA)") (class "Default")
      (node (ref "D30") (pin "A") (pinfunction "A_A") (pintype "passive"))
      (node (ref "D31") (pin "C") (pinfunction "C_C") (pintype "passive"))
    )
    (net (code "39") (name "Net-(D36-PadC)") (class "Default")
      (node (ref "D36") (pin "C") (pinfunction "C_C") (pintype "passive"))
      (node (ref "D37") (pin "C") (pinfunction "C_C") (pintype "passive"))
      (node (ref "R19") (pin "2") (pinfunction "2_2") (pintype "passive"))
    )
    (net (code "40") (name "Net-(D37-PadA)") (class "Default")
      (node (ref "D37") (pin "A") (pinfunction "A_A") (pintype "passive"))
      (node (ref "D38") (pin "C") (pinfunction "C_C") (pintype "passive"))
    )
    (net (code "41") (name "Net-(D51-PadC)") (class "Default")
      (node (ref "D51") (pin "C") (pinfunction "C_C") (pintype "passive"))
      (node (ref "D52") (pin "C") (pinfunction "C_C") (pintype "passive"))
      (node (ref "D55") (pin "C") (pinfunction "C_C") (pintype "passive"))
      (node (ref "R27") (pin "2") (pinfunction "2_2") (pintype "passive"))
    )
    (net (code "42") (name "Net-(D52-PadA)") (class "Default")
      (node (ref "D52") (pin "A") (pinfunction "A_A") (pintype "passive"))
      (node (ref "D53") (pin "C") (pinfunction "C_C") (pintype "passive"))
    )
    (net (code "43") (name "Net-(D58-PadC)") (class "Default")
      (node (ref "D58") (pin "C") (pinfunction "C_C") (pintype "passive"))
      (node (ref "D59") (pin "C") (pinfunction "C_C") (pintype "passive"))
      (node (ref "R31") (pin "2") (pinfunction "2_2") (pintype "passive"))
    )
    (net (code "44") (name "Net-(D59-PadA)") (class "Default")
      (node (ref "D59") (pin "A") (pinfunction "A_A") (pintype "passive"))
      (node (ref "D60") (pin "C") (pinfunction "C_C") (pintype "passive"))
    )
    (net (code "45") (name "Net-(D71-PadA)") (class "Default")
      (node (ref "D71") (pin "A") (pinfunction "A_A") (pintype "passive"))
      (node (ref "D72") (pin "C") (pinfunction "C_C") (pintype "passive"))
    )
    (net (code "46") (name "Net-(D72-PadA)") (class "Default")
      (node (ref "D72") (pin "A") (pinfunction "A_A") (pintype "passive"))
      (node (ref "D73") (pin "C") (pinfunction "C_C") (pintype "passive"))
    )
    (net (code "47") (name "Net-(Q1-B)") (class "Default")
      (node (ref "D3") (pin "C") (pinfunction "C_C") (pintype "passive"))
      (node (ref "D8") (pin "A") (pinfunction "A_A") (pintype "passive"))
      (node (ref "Q1") (pin "2") (pinfunction "B_2") (pintype "passive"))
      (node (ref "R4") (pin "1") (pinfunction "1_1") (pintype "passive"))
    )
    (net (code "48") (name "Net-(Q2-B)") (class "Default")
      (node (ref "D15") (pin "A") (pinfunction "A_A") (pintype "passive"))
      (node (ref "D18") (pin "C") (pinfunction "C_C") (pintype "passive"))
      (node (ref "D21") (pin "C") (pinfunction "C_C") (pintype "passive"))
      (node (ref "Q2") (pin "2") (pinfunction "B_2") (pintype "passive"))
      (node (ref "R7") (pin "1") (pinfunction "1_1") (pintype "passive"))
    )
    (net (code "49") (name "Net-(Q3-B)") (class "Default")
      (node (ref "D28") (pin "C") (pinfunction "C_C") (pintype "passive"))
      (node (ref "D31") (pin "A") (pinfunction "A_A") (pintype "passive"))
      (node (ref "Q3") (pin "2") (pinfunction "B_2") (pintype "passive"))
      (node (ref "R16") (pin "1") (pinfunction "1_1") (pintype "passive"))
    )
    (net (code "50") (name "Net-(Q4-B)") (class "Default")
      (node (ref "D38") (pin "A") (pinfunction "A_A") (pintype "passive"))
      (node (ref "D41") (pin "C") (pinfunction "C_C") (pintype "passive"))
      (node (ref "D44") (pin "C") (pinfunction "C_C") (pintype "passive"))
      (node (ref "Q4") (pin "2") (pinfunction "B_2") (pintype "passive"))
      (node (ref "R20") (pin "1") (pinfunction "1_1") (pintype "passive"))
    )
    (net (code "51") (name "Net-(Q5-B)") (class "Default")
      (node (ref "D50") (pin "C") (pinfunction "C_C") (pintype "passive"))
      (node (ref "D53") (pin "A") (pinfunction "A_A") (pintype "passive"))
      (node (ref "Q5") (pin "2") (pinfunction "B_2") (pintype "passive"))
      (node (ref "R28") (pin "1") (pinfunction "1_1") (pintype "passive"))
    )
    (net (code "52") (name "Net-(Q6-B)") (class "Default")
      (node (ref "D60") (pin "A") (pinfunction "A_A") (pintype "passive"))
      (node (ref "D64") (pin "C") (pinfunction "C_C") (pintype "passive"))
      (node (ref "D65") (pin "C") (pinfunction "C_C") (pintype "passive"))
      (node (ref "Q6") (pin "2") (pinfunction "B_2") (pintype "passive"))
      (node (ref "R32") (pin "1") (pinfunction "1_1") (pintype "passive"))
    )
    (net (code "53") (name "Net-(U$2H-1)") (class "Default")
      (node (ref "D11") (pin "C") (pinfunction "C_C") (pintype "passive"))
      (node (ref "D34") (pin "C") (pinfunction "C_C") (pintype "passive"))
      (node (ref "D56") (pin "C") (pinfunction "C_C") (pintype "passive"))
      (node (ref "U$2") (pin "J2") (pinfunction "1_J2") (pintype "bidirectional"))
    )
    (net (code "54") (name "Net-(U$2J-1)") (class "Default")
      (node (ref "D16") (pin "A") (pinfunction "A_A") (pintype "passive"))
      (node (ref "D19") (pin "A") (pinfunction "A_A") (pintype "passive"))
      (node (ref "U$2") (pin "L2") (pinfunction "1_L2") (pintype "bidirectional"))
    )
    (net (code "55") (name "Net-(U$2K-1)") (class "Default")
      (node (ref "D4") (pin "A") (pinfunction "A_A") (pintype "passive"))
      (node (ref "D5") (pin "A") (pinfunction "A_A") (pintype "passive"))
      (node (ref "U$2") (pin "M2") (pinfunction "1_M2") (pintype "bidirectional"))
    )
    (net (code "56") (name "Net-(U$2M-1)") (class "Default")
      (node (ref "D17") (pin "A") (pinfunction "A_A") (pintype "passive"))
      (node (ref "D20") (pin "A") (pinfunction "A_A") (pintype "passive"))
      (node (ref "U$2") (pin "P2") (pinfunction "1_P2") (pintype "bidirectional"))
    )
    (net (code "57") (name "Net-(U$2N-1)") (class "Default")
      (node (ref "D40") (pin "A") (pinfunction "A_A") (pintype "passive"))
      (node (ref "D43") (pin "A") (pinfunction "A_A") (pintype "passive"))
      (node (ref "U$2") (pin "R2") (pinfunction "1_R2") (pintype "bidirectional"))
    )
    (net (code "58") (name "Net-(U$2O-1)") (class "Default")
      (node (ref "D61") (pin "A") (pinfunction "A_A") (pintype "passive"))
      (node (ref "D63") (pin "A") (pinfunction "A_A") (pintype "passive"))
      (node (ref "U$2") (pin "S2") (pinfunction "1_S2") (pintype "bidirectional"))
    )
  )
)
